# April12_RevB.net
KiCad netlist of a schematic drawn in Altium Designer
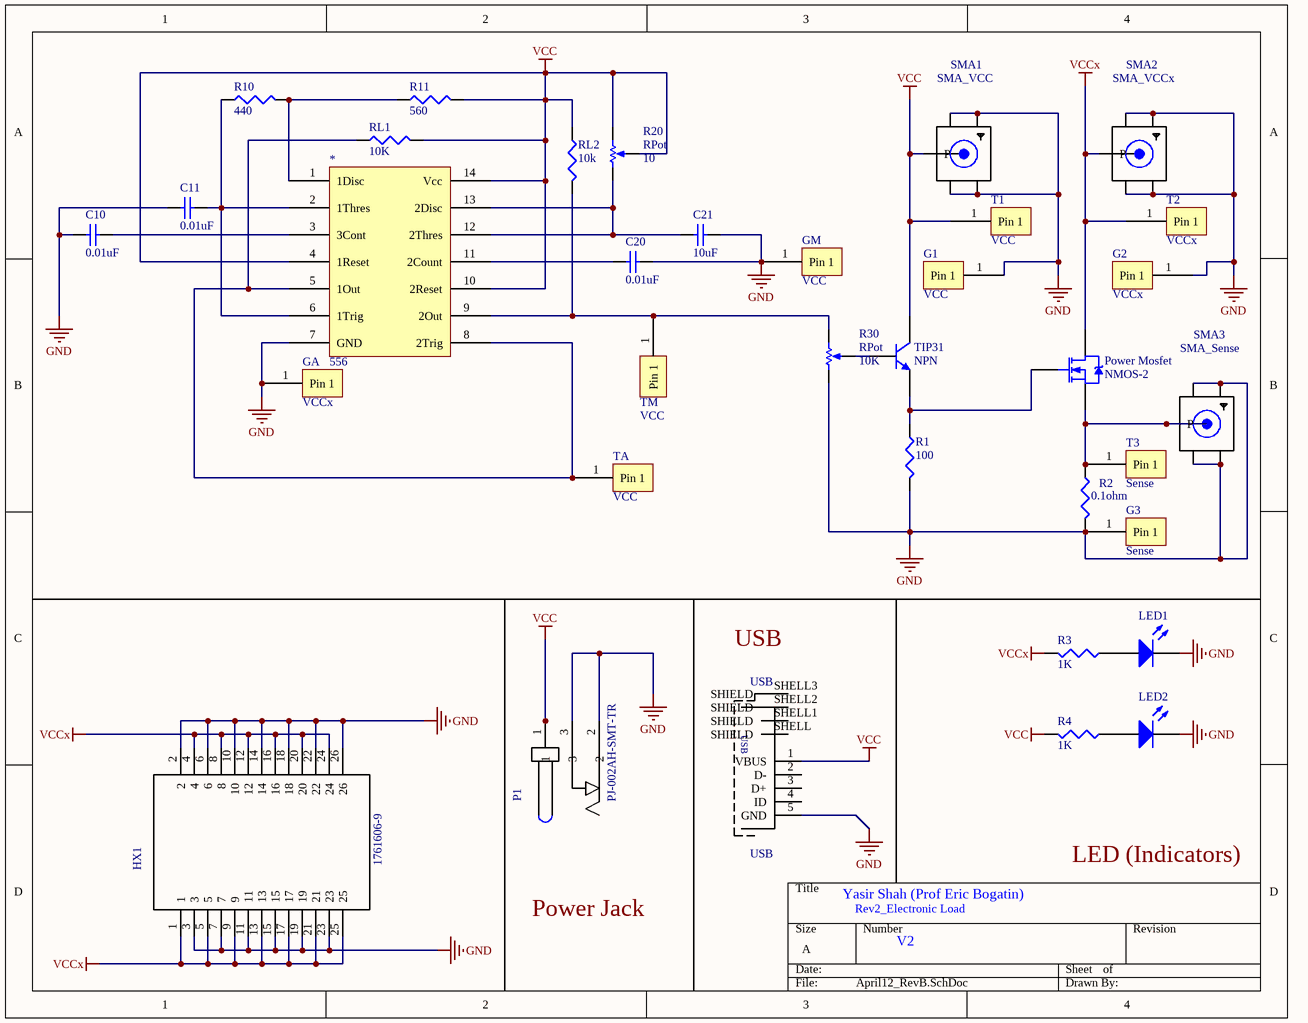
[diagram p0: April12_RevB.SchDoc]

(export (version "E")
  (design (tool "Eeschema 10.0.6"))
  (components
    (comp (ref "*") (value "556") (footprint "556 timer") (libsource (lib "Schematic_Library") (part "556")))
    (comp (ref "C10")
      (value "0.01uF")
      (footprint "CAPC2012X140N")
      (description "Capacitor (Semiconductor SIM Model)")
      (fields (field (name "Comment") "Cap Semi") (field (name "PUBLISHER") "Altium Limited"))
      (libsource (lib "Miscellaneous Devices") (part "Cap Semi"))
    )
    (comp (ref "C11")
      (value "0.01uF")
      (footprint "CAPC2012X140N")
      (description "Capacitor (Semiconductor SIM Model)")
      (fields (field (name "Comment") "Cap Semi") (field (name "PUBLISHER") "Altium Limited"))
      (libsource (lib "Miscellaneous Devices") (part "Cap Semi"))
    )
    (comp (ref "C20")
      (value "0.01uF")
      (footprint "CAPC2012X140N")
      (description "Capacitor (Semiconductor SIM Model)")
      (fields (field (name "Comment") "Cap Semi") (field (name "PUBLISHER") "Altium Limited"))
      (libsource (lib "Miscellaneous Devices") (part "Cap Semi"))
    )
    (comp (ref "C21")
      (value "10uF")
      (footprint "CAPC2012X140N")
      (description "Capacitor (Semiconductor SIM Model)")
      (fields (field (name "Comment") "Cap Semi") (field (name "PUBLISHER") "Altium Limited"))
      (libsource (lib "Miscellaneous Devices") (part "Cap Semi"))
    )
    (comp (ref "G1")
      (value "VCC")
      (footprint "1Pin Header")
      (libsource (lib "SchematicLibrary") (part "1Pin Header"))
    )
    (comp (ref "G2")
      (value "VCCx")
      (footprint "1Pin Header")
      (libsource (lib "SchematicLibrary") (part "1Pin Header"))
    )
    (comp (ref "G3") (value "Sense") (footprint "1Pin Header") (libsource (lib "") (part "1Pin Header_1")))
    (comp (ref "GA") (value "VCCx") (footprint "1Pin Header") (libsource (lib "") (part "1Pin Header_1")))
    (comp (ref "GM") (value "VCC") (footprint "1Pin Header") (libsource (lib "") (part "1Pin Header_1")))
    (comp (ref "HX1")
      (value "1761606-9")
      (footprint "TYCO_1761606-9")
      (description "Header, Pin, Idc, Amp-Latch, 26 Pos, Low Profile, Pcb, Vertical, Black")
      (fields (field (name "MF") "TE Connectivity"))
      (libsource (lib "1761606-9") (part "1761606-9"))
    )
    (comp (ref "LED1")
      (value "LED2")
      (footprint "C1206")
      (description "Typical RED, GREEN, YELLOW, AMBER GaAs LED")
      (fields (field (name "PUBLISHER") "Altium Limited"))
      (libsource (lib "Miscellaneous Devices") (part "LED2"))
    )
    (comp (ref "LED2")
      (value "LED2")
      (footprint "C1206")
      (description "Typical RED, GREEN, YELLOW, AMBER GaAs LED")
      (fields (field (name "PUBLISHER") "Altium Limited"))
      (libsource (lib "Miscellaneous Devices") (part "LED2"))
    )
    (comp (ref "P1")
      (value "PJ-002AH-SMT-TR")
      (footprint "CUI_PJ-002AH-SMT-TR")
      (description "24 VDC 5 A Surface Mount Unshielded 2 Conductors 3 Contacts Male Power Jack")
      (fields (field (name "MF") "CUI"))
      (libsource (lib "PJ-002AH-SMT-TR") (part "PJ-002AH-SMT-TR"))
    )
    (comp (ref "Power Mosfet")
      (value "NMOS-2")
      (footprint "TO-220AB")
      (description "N-Channel Power MOSFET")
      (fields (field (name "PUBLISHER") "Altium Limited"))
      (libsource (lib "Miscellaneous Devices") (part "NMOS-2"))
    )
    (comp (ref "R1")
      (value "100")
      (footprint "RESC2012X70")
      (description "Resistor")
      (fields (field (name "Comment") "Res3") (field (name "PUBLISHER") "Altium Limited"))
      (libsource (lib "Miscellaneous Devices") (part "Res3"))
    )
    (comp (ref "R2")
      (value "0.1ohm")
      (footprint "RESC3216X65")
      (description "Resistor")
      (fields (field (name "PUBLISHER") "Altium Limited"))
      (libsource (lib "Miscellaneous Devices") (part "Res3"))
    )
    (comp (ref "R3")
      (value "1K")
      (footprint "RESC2012X70")
      (description "Resistor")
      (fields (field (name "Comment") "Res3") (field (name "PUBLISHER") "Altium Limited"))
      (libsource (lib "Miscellaneous Devices") (part "Res3"))
    )
    (comp (ref "R4")
      (value "1K")
      (footprint "RESC2012X70")
      (description "Resistor")
      (fields (field (name "Comment") "Res3") (field (name "PUBLISHER") "Altium Limited"))
      (libsource (lib "Miscellaneous Devices") (part "Res3"))
    )
    (comp (ref "R10")
      (value "440")
      (footprint "RESC2012X70")
      (description "Resistor")
      (fields (field (name "Comment") "Res3") (field (name "PUBLISHER") "Altium Limited"))
      (libsource (lib "Miscellaneous Devices") (part "Res3"))
    )
    (comp (ref "R11")
      (value "560")
      (footprint "RESC2012X70")
      (description "Resistor")
      (fields (field (name "Comment") "Res3") (field (name "PUBLISHER") "Altium Limited"))
      (libsource (lib "Miscellaneous Devices") (part "Res3"))
    )
    (comp (ref "R20")
      (value "RPot")
      (footprint "VR5")
      (description "Potentiometer")
      (fields (field (name "ALTIUM_VALUE") "10") (field (name "PUBLISHER") "Altium Limited"))
      (libsource (lib "Miscellaneous Devices") (part "RPot"))
    )
    (comp (ref "R30")
      (value "RPot")
      (footprint "VR5")
      (description "Potentiometer")
      (fields (field (name "ALTIUM_VALUE") "10K") (field (name "PUBLISHER") "Altium Limited"))
      (libsource (lib "Miscellaneous Devices") (part "RPot"))
    )
    (comp (ref "RL1")
      (value "10K")
      (footprint "RESC2012X70")
      (description "Resistor")
      (fields (field (name "Comment") "Res3") (field (name "PUBLISHER") "Altium Limited"))
      (libsource (lib "Miscellaneous Devices") (part "Res3"))
    )
    (comp (ref "RL2")
      (value "10k")
      (footprint "RESC2012X70")
      (description "Resistor")
      (fields (field (name "Comment") "Res3") (field (name "PUBLISHER") "Altium Limited"))
      (libsource (lib "Miscellaneous Devices") (part "Res3"))
    )
    (comp (ref "SMA_Sense")
      (value "SMA3")
      (footprint "sma_UserDefined")
      (description "Edge-Launch SMA Connector for 1.6mm / 0.062 Thick PCBs")
      (fields (field (name "MP") "1865") (field (name "MF") "Keystone"))
      (libsource (lib "1865") (part "1865"))
    )
    (comp (ref "SMA_VCC")
      (value "SMA1")
      (footprint "sma_UserDefined")
      (description "Edge-Launch SMA Connector for 1.6mm / 0.062 Thick PCBs")
      (fields (field (name "MP") "1865") (field (name "MF") "Keystone"))
      (libsource (lib "1865") (part "1865"))
    )
    (comp (ref "SMA_VCCx")
      (value "SMA2")
      (footprint "sma_UserDefined")
      (description "Edge-Launch SMA Connector for 1.6mm / 0.062 Thick PCBs")
      (fields (field (name "MP") "1865") (field (name "MF") "Keystone"))
      (libsource (lib "1865") (part "1865"))
    )
    (comp (ref "T1") (value "VCC") (footprint "1Pin Header") (libsource (lib "") (part "1Pin Header_1")))
    (comp (ref "T2") (value "VCCx") (footprint "1Pin Header") (libsource (lib "") (part "1Pin Header_1")))
    (comp (ref "T3") (value "Sense") (footprint "1Pin Header") (libsource (lib "") (part "1Pin Header_1")))
    (comp (ref "TA") (value "VCC") (footprint "1Pin Header") (libsource (lib "") (part "1Pin Header_1")))
    (comp (ref "TIP31")
      (value "NPN")
      (footprint "TO-226-AA")
      (description "NPN Bipolar Transistor")
      (fields (field (name "PUBLISHER") "Altium Limited"))
      (libsource (lib "Miscellaneous Devices") (part "NPN"))
    )
    (comp (ref "TM") (value "VCC") (footprint "1Pin Header") (libsource (lib "") (part "1Pin Header_2")))
    (comp (ref "USB")
      (value "USB")
      (footprint "651005136521_651005136521(Primary)")
      (description "MINI USB A - 5POS Horizontal through hole")
      (fields (field (name "MF") "Wurth Electronics") (field (name "MP") "651005136521"))
      (libsource (lib "651005136521") (part "651005136521"))
    )
  )
  (nets
    (net (code "1") (name "GND") (class "Default")
      (node (ref "*") (pin "7") (pinfunction "GND_7") (pintype "passive"))
      (node (ref "C10") (pin "2") (pinfunction "2_2") (pintype "passive"))
      (node (ref "C11") (pin "2") (pinfunction "2_2") (pintype "passive"))
      (node (ref "C20") (pin "1") (pinfunction "1_1") (pintype "passive"))
      (node (ref "C21") (pin "1") (pinfunction "1_1") (pintype "passive"))
      (node (ref "G1") (pin "1") (pinfunction "Pin_1_1") (pintype "passive"))
      (node (ref "G2") (pin "1") (pinfunction "Pin_1_1") (pintype "passive"))
      (node (ref "G3") (pin "1") (pinfunction "Pin_1_1") (pintype "passive"))
      (node (ref "GA") (pin "1") (pinfunction "Pin_1_1") (pintype "passive"))
      (node (ref "GM") (pin "1") (pinfunction "Pin_1_1") (pintype "passive"))
      (node (ref "HX1") (pin "10") (pinfunction "10_10") (pintype "passive"))
      (node (ref "HX1") (pin "11") (pinfunction "11_11") (pintype "passive"))
      (node (ref "HX1") (pin "14") (pinfunction "14_14") (pintype "passive"))
      (node (ref "HX1") (pin "15") (pinfunction "15_15") (pintype "passive"))
      (node (ref "HX1") (pin "18") (pinfunction "18_18") (pintype "passive"))
      (node (ref "HX1") (pin "19") (pinfunction "19_19") (pintype "passive"))
      (node (ref "HX1") (pin "2") (pinfunction "2_2") (pintype "passive"))
      (node (ref "HX1") (pin "22") (pinfunction "22_22") (pintype "passive"))
      (node (ref "HX1") (pin "23") (pinfunction "23_23") (pintype "passive"))
      (node (ref "HX1") (pin "26") (pinfunction "26_26") (pintype "passive"))
      (node (ref "HX1") (pin "3") (pinfunction "3_3") (pintype "passive"))
      (node (ref "HX1") (pin "6") (pinfunction "6_6") (pintype "passive"))
      (node (ref "HX1") (pin "7") (pinfunction "7_7") (pintype "passive"))
      (node (ref "LED1") (pin "2") (pinfunction "K_2") (pintype "passive"))
      (node (ref "LED2") (pin "2") (pinfunction "K_2") (pintype "passive"))
      (node (ref "P1") (pin "2") (pinfunction "2_2") (pintype "passive"))
      (node (ref "P1") (pin "3") (pinfunction "3_3") (pintype "passive"))
      (node (ref "R1") (pin "2") (pinfunction "2_2") (pintype "passive"))
      (node (ref "R2") (pin "2") (pinfunction "2_2") (pintype "passive"))
      (node (ref "R30") (pin "1") (pinfunction "TOP_1") (pintype "passive"))
      (node (ref "SMA_Sense") (pin "GND1") (pinfunction "GND1_GND1") (pintype "power_in"))
      (node (ref "SMA_Sense") (pin "GND2") (pinfunction "GND2_GND2") (pintype "power_in"))
      (node (ref "SMA_Sense") (pin "GND3") (pinfunction "GND3_GND3") (pintype "power_in"))
      (node (ref "SMA_Sense") (pin "GND4") (pinfunction "GND4_GND4") (pintype "power_in"))
      (node (ref "SMA_VCC") (pin "GND1") (pinfunction "GND1_GND1") (pintype "power_in"))
      (node (ref "SMA_VCC") (pin "GND2") (pinfunction "GND2_GND2") (pintype "power_in"))
      (node (ref "SMA_VCC") (pin "GND3") (pinfunction "GND3_GND3") (pintype "power_in"))
      (node (ref "SMA_VCC") (pin "GND4") (pinfunction "GND4_GND4") (pintype "power_in"))
      (node (ref "SMA_VCCx") (pin "GND1") (pinfunction "GND1_GND1") (pintype "power_in"))
      (node (ref "SMA_VCCx") (pin "GND2") (pinfunction "GND2_GND2") (pintype "power_in"))
      (node (ref "SMA_VCCx") (pin "GND3") (pinfunction "GND3_GND3") (pintype "power_in"))
      (node (ref "SMA_VCCx") (pin "GND4") (pinfunction "GND4_GND4") (pintype "power_in"))
      (node (ref "USB") (pin "5") (pinfunction "GND_5") (pintype "passive"))
    )
    (net (code "2") (name "Net-(*-1Disc)") (class "Default")
      (node (ref "*") (pin "1") (pinfunction "1Disc_1") (pintype "passive"))
      (node (ref "R10") (pin "2") (pinfunction "2_2") (pintype "passive"))
      (node (ref "R11") (pin "1") (pinfunction "1_1") (pintype "passive"))
    )
    (net (code "3") (name "Net-(*-1Out)") (class "Default")
      (node (ref "*") (pin "5") (pinfunction "1Out_5") (pintype "passive"))
      (node (ref "*") (pin "8") (pinfunction "2Trig_8") (pintype "passive"))
      (node (ref "RL1") (pin "1") (pinfunction "1_1") (pintype "passive"))
      (node (ref "TA") (pin "1") (pinfunction "Pin_1_1") (pintype "passive"))
    )
    (net (code "4") (name "Net-(*-1Thres)") (class "Default")
      (node (ref "*") (pin "2") (pinfunction "1Thres_2") (pintype "passive"))
      (node (ref "*") (pin "6") (pinfunction "1Trig_6") (pintype "passive"))
      (node (ref "C11") (pin "1") (pinfunction "1_1") (pintype "passive"))
      (node (ref "R10") (pin "1") (pinfunction "1_1") (pintype "passive"))
    )
    (net (code "5") (name "Net-(*-2Count)") (class "Default")
      (node (ref "*") (pin "11") (pinfunction "2Count_11") (pintype "passive"))
      (node (ref "C20") (pin "2") (pinfunction "2_2") (pintype "passive"))
    )
    (net (code "6") (name "Net-(*-2Disc)") (class "Default")
      (node (ref "*") (pin "12") (pinfunction "2Thres_12") (pintype "passive"))
      (node (ref "*") (pin "13") (pinfunction "2Disc_13") (pintype "passive"))
      (node (ref "C21") (pin "2") (pinfunction "2_2") (pintype "passive"))
      (node (ref "R20") (pin "1") (pinfunction "TOP_1") (pintype "passive"))
    )
    (net (code "7") (name "Net-(*-2Out)") (class "Default")
      (node (ref "*") (pin "9") (pinfunction "2Out_9") (pintype "passive"))
      (node (ref "R30") (pin "2") (pinfunction "BOT_2") (pintype "passive"))
      (node (ref "RL2") (pin "2") (pinfunction "2_2") (pintype "passive"))
      (node (ref "TM") (pin "1") (pinfunction "Pin_1_1") (pintype "passive"))
    )
    (net (code "8") (name "Net-(*-3Cont)") (class "Default")
      (node (ref "*") (pin "3") (pinfunction "3Cont_3") (pintype "passive"))
      (node (ref "C10") (pin "1") (pinfunction "1_1") (pintype "passive"))
    )
    (net (code "9") (name "Net-(LED1-A)") (class "Default")
      (node (ref "LED1") (pin "1") (pinfunction "A_1") (pintype "passive"))
      (node (ref "R3") (pin "1") (pinfunction "1_1") (pintype "passive"))
    )
    (net (code "10") (name "Net-(LED2-A)") (class "Default")
      (node (ref "LED2") (pin "1") (pinfunction "A_1") (pintype "passive"))
      (node (ref "R4") (pin "1") (pinfunction "1_1") (pintype "passive"))
    )
    (net (code "11") (name "Net-(Power Mosfet-G)") (class "Default")
      (node (ref "Power Mosfet") (pin "1") (pinfunction "G_1") (pintype "passive"))
      (node (ref "R1") (pin "1") (pinfunction "1_1") (pintype "passive"))
      (node (ref "TIP31") (pin "3") (pinfunction "E_3") (pintype "passive"))
    )
    (net (code "12") (name "Net-(Power Mosfet-S)") (class "Default")
      (node (ref "Power Mosfet") (pin "3") (pinfunction "S_3") (pintype "passive"))
      (node (ref "R2") (pin "1") (pinfunction "1_1") (pintype "passive"))
      (node (ref "SMA_Sense") (pin "P") (pinfunction "P_P") (pintype "bidirectional"))
      (node (ref "T3") (pin "1") (pinfunction "Pin_1_1") (pintype "passive"))
    )
    (net (code "13") (name "Net-(R30-TAP)") (class "Default")
      (node (ref "R30") (pin "3") (pinfunction "TAP_3") (pintype "passive"))
      (node (ref "TIP31") (pin "2") (pinfunction "B_2") (pintype "passive"))
    )
    (net (code "14") (name "VCC") (class "Default")
      (node (ref "*") (pin "10") (pinfunction "2Reset_10") (pintype "passive"))
      (node (ref "*") (pin "14") (pinfunction "Vcc_14") (pintype "passive"))
      (node (ref "*") (pin "4") (pinfunction "1Reset_4") (pintype "passive"))
      (node (ref "P1") (pin "1") (pinfunction "1_1") (pintype "passive"))
      (node (ref "R11") (pin "2") (pinfunction "2_2") (pintype "passive"))
      (node (ref "R20") (pin "2") (pinfunction "BOT_2") (pintype "passive"))
      (node (ref "R20") (pin "3") (pinfunction "TAP_3") (pintype "passive"))
      (node (ref "R4") (pin "2") (pinfunction "2_2") (pintype "passive"))
      (node (ref "RL1") (pin "2") (pinfunction "2_2") (pintype "passive"))
      (node (ref "RL2") (pin "1") (pinfunction "1_1") (pintype "passive"))
      (node (ref "SMA_VCC") (pin "P") (pinfunction "P_P") (pintype "bidirectional"))
      (node (ref "T1") (pin "1") (pinfunction "Pin_1_1") (pintype "passive"))
      (node (ref "TIP31") (pin "1") (pinfunction "C_1") (pintype "passive"))
      (node (ref "USB") (pin "1") (pinfunction "VBUS_1") (pintype "passive"))
    )
    (net (code "15") (name "VCCx") (class "Default")
      (node (ref "HX1") (pin "1") (pinfunction "1_1") (pintype "passive"))
      (node (ref "HX1") (pin "12") (pinfunction "12_12") (pintype "passive"))
      (node (ref "HX1") (pin "13") (pinfunction "13_13") (pintype "passive"))
      (node (ref "HX1") (pin "16") (pinfunction "16_16") (pintype "passive"))
      (node (ref "HX1") (pin "17") (pinfunction "17_17") (pintype "passive"))
      (node (ref "HX1") (pin "20") (pinfunction "20_20") (pintype "passive"))
      (node (ref "HX1") (pin "21") (pinfunction "21_21") (pintype "passive"))
      (node (ref "HX1") (pin "24") (pinfunction "24_24") (pintype "passive"))
      (node (ref "HX1") (pin "25") (pinfunction "25_25") (pintype "passive"))
      (node (ref "HX1") (pin "4") (pinfunction "4_4") (pintype "passive"))
      (node (ref "HX1") (pin "5") (pinfunction "5_5") (pintype "passive"))
      (node (ref "HX1") (pin "8") (pinfunction "8_8") (pintype "passive"))
      (node (ref "HX1") (pin "9") (pinfunction "9_9") (pintype "passive"))
      (node (ref "Power Mosfet") (pin "2") (pinfunction "D_2") (pintype "passive"))
      (node (ref "R3") (pin "2") (pinfunction "2_2") (pintype "passive"))
      (node (ref "SMA_VCCx") (pin "P") (pinfunction "P_P") (pintype "bidirectional"))
      (node (ref "T2") (pin "1") (pinfunction "Pin_1_1") (pintype "passive"))
    )
    (net (code "16") (name "unconnected-(USB-D+-Pad3)") (class "Default")
      (node (ref "USB") (pin "3") (pinfunction "D+_3") (pintype "passive"))
    )
    (net (code "17") (name "unconnected-(USB-D--Pad2)") (class "Default")
      (node (ref "USB") (pin "2") (pinfunction "D-_2") (pintype "passive"))
    )
    (net (code "18") (name "unconnected-(USB-ID-Pad4)") (class "Default")
      (node (ref "USB") (pin "4") (pinfunction "ID_4") (pintype "passive"))
    )
    (net (code "19") (name "unconnected-(USB-SHIELD-PadSHELL)") (class "Default")
      (node (ref "USB") (pin "SHELL") (pinfunction "SHIELD_SHELL") (pintype "passive"))
    )
    (net (code "20") (name "unconnected-(USB-SHIELD-PadSHELL1)") (class "Default")
      (node (ref "USB") (pin "SHELL1") (pinfunction "SHIELD_SHELL1") (pintype "passive"))
    )
    (net (code "21") (name "unconnected-(USB-SHIELD-PadSHELL2)") (class "Default")
      (node (ref "USB") (pin "SHELL2") (pinfunction "SHIELD_SHELL2") (pintype "passive"))
    )
    (net (code "22") (name "unconnected-(USB-SHIELD-PadSHELL3)") (class "Default")
      (node (ref "USB") (pin "SHELL3") (pinfunction "SHIELD_SHELL3") (pintype "passive"))
    )
  )
)
